# outsim_nano.net
KiCad netlist of a schematic drawn in EAGLE
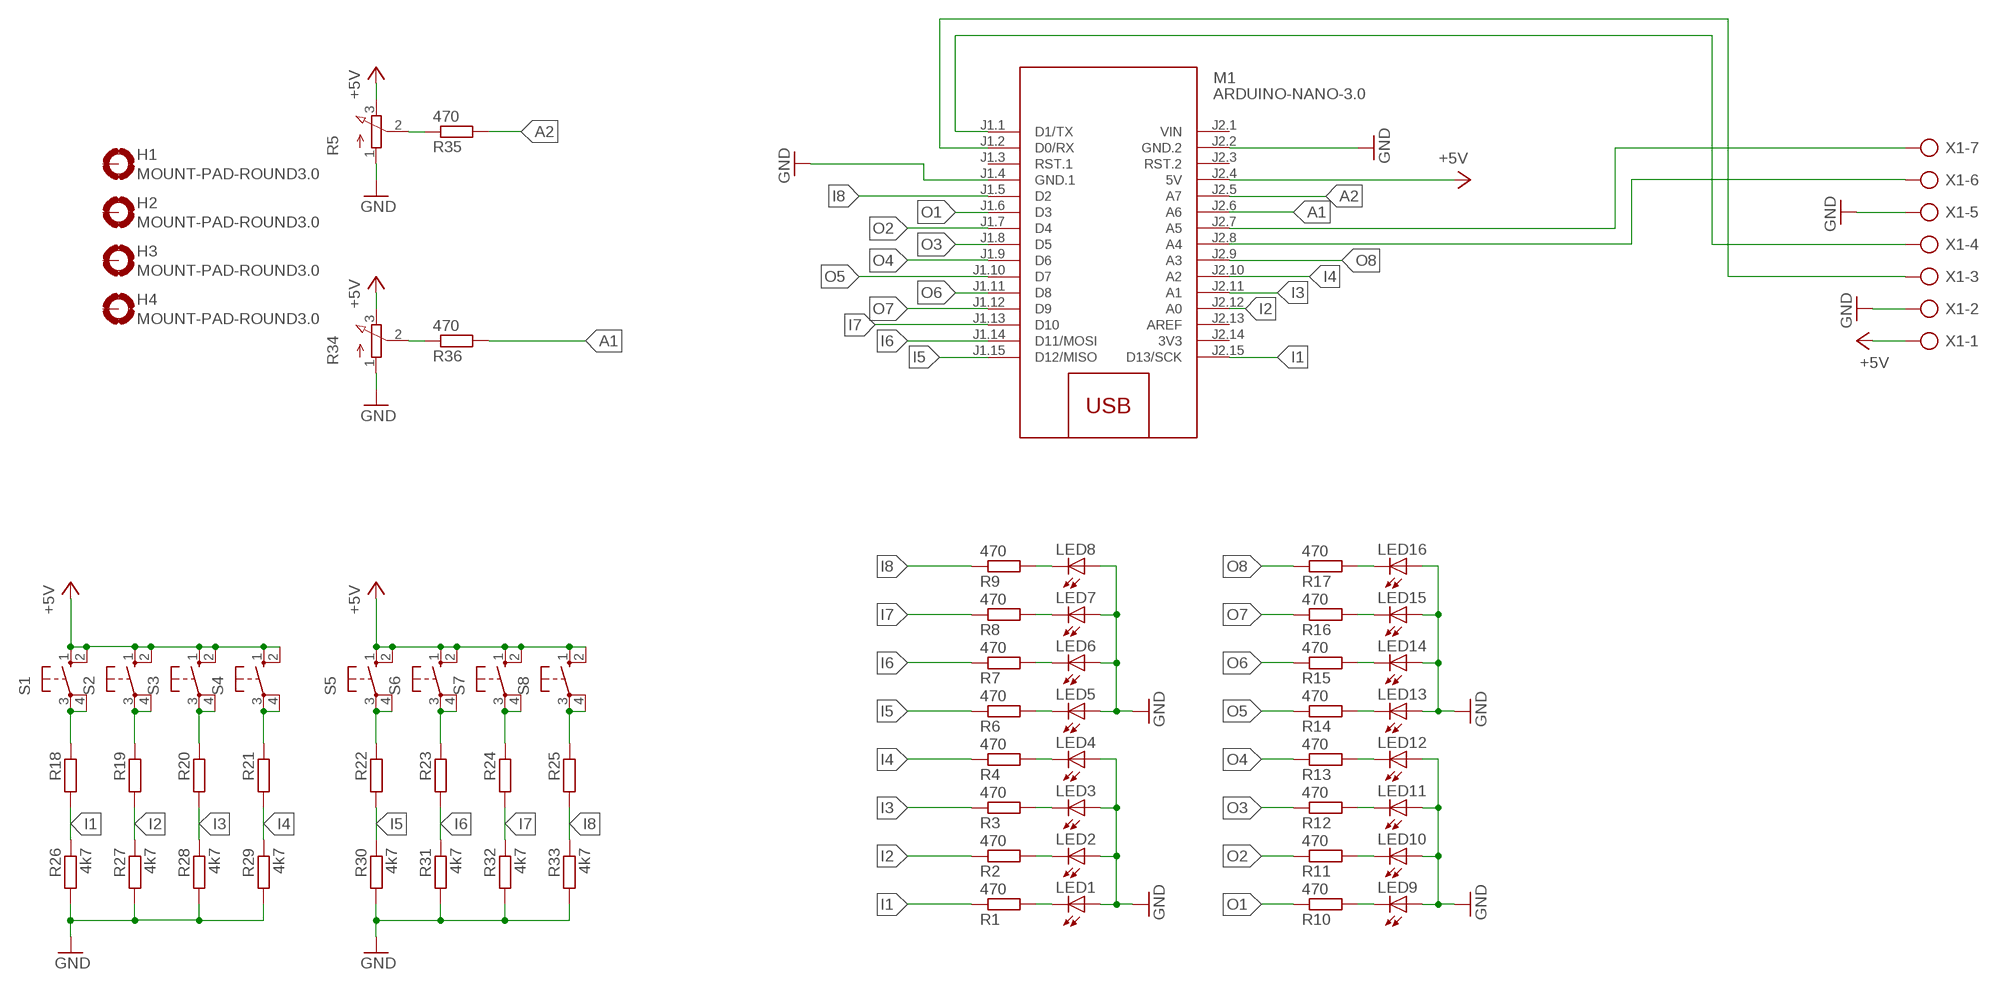
[diagram p0: schematic, sheet 1]

(export (version "E")
  (design (tool "Eeschema 10.0.6"))
  (components
    (comp (ref "H1")
      (value "MOUNT-PAD-ROUND3.0")
      (footprint "eagle-import:3,0-PAD")
      (libsource (lib "eagle-import") (part "MOUNT-PAD-ROUND3.0"))
    )
    (comp (ref "H2")
      (value "MOUNT-PAD-ROUND3.0")
      (footprint "eagle-import:3,0-PAD")
      (libsource (lib "eagle-import") (part "MOUNT-PAD-ROUND3.0"))
    )
    (comp (ref "H3")
      (value "MOUNT-PAD-ROUND3.0")
      (footprint "eagle-import:3,0-PAD")
      (libsource (lib "eagle-import") (part "MOUNT-PAD-ROUND3.0"))
    )
    (comp (ref "H4")
      (value "MOUNT-PAD-ROUND3.0")
      (footprint "eagle-import:3,0-PAD")
      (libsource (lib "eagle-import") (part "MOUNT-PAD-ROUND3.0"))
    )
    (comp (ref "LED1")
      (value "LED5MM")
      (footprint "eagle-import:LED5MM")
      (libsource (lib "eagle-import") (part "LED5MM"))
    )
    (comp (ref "LED2")
      (value "LED5MM")
      (footprint "eagle-import:LED5MM")
      (libsource (lib "eagle-import") (part "LED5MM"))
    )
    (comp (ref "LED3")
      (value "LED5MM")
      (footprint "eagle-import:LED5MM")
      (libsource (lib "eagle-import") (part "LED5MM"))
    )
    (comp (ref "LED4")
      (value "LED5MM")
      (footprint "eagle-import:LED5MM")
      (libsource (lib "eagle-import") (part "LED5MM"))
    )
    (comp (ref "LED5")
      (value "LED5MM")
      (footprint "eagle-import:LED5MM")
      (libsource (lib "eagle-import") (part "LED5MM"))
    )
    (comp (ref "LED6")
      (value "LED5MM")
      (footprint "eagle-import:LED5MM")
      (libsource (lib "eagle-import") (part "LED5MM"))
    )
    (comp (ref "LED7")
      (value "LED5MM")
      (footprint "eagle-import:LED5MM")
      (libsource (lib "eagle-import") (part "LED5MM"))
    )
    (comp (ref "LED8")
      (value "LED5MM")
      (footprint "eagle-import:LED5MM")
      (libsource (lib "eagle-import") (part "LED5MM"))
    )
    (comp (ref "LED9")
      (value "LED5MM")
      (footprint "eagle-import:LED5MM")
      (libsource (lib "eagle-import") (part "LED5MM"))
    )
    (comp (ref "LED10")
      (value "LED5MM")
      (footprint "eagle-import:LED5MM")
      (libsource (lib "eagle-import") (part "LED5MM"))
    )
    (comp (ref "LED11")
      (value "LED5MM")
      (footprint "eagle-import:LED5MM")
      (libsource (lib "eagle-import") (part "LED5MM"))
    )
    (comp (ref "LED12")
      (value "LED5MM")
      (footprint "eagle-import:LED5MM")
      (libsource (lib "eagle-import") (part "LED5MM"))
    )
    (comp (ref "LED13")
      (value "LED5MM")
      (footprint "eagle-import:LED5MM")
      (libsource (lib "eagle-import") (part "LED5MM"))
    )
    (comp (ref "LED14")
      (value "LED5MM")
      (footprint "eagle-import:LED5MM")
      (libsource (lib "eagle-import") (part "LED5MM"))
    )
    (comp (ref "LED15")
      (value "LED5MM")
      (footprint "eagle-import:LED5MM")
      (libsource (lib "eagle-import") (part "LED5MM"))
    )
    (comp (ref "LED16")
      (value "LED5MM")
      (footprint "eagle-import:LED5MM")
      (libsource (lib "eagle-import") (part "LED5MM"))
    )
    (comp (ref "M1")
      (value "ARDUINO-NANO-3.0")
      (footprint "eagle-import:ARDUINO-NANO-3.0")
      (libsource (lib "eagle-import") (part "ARDUINO-NANO-3.0"))
    )
    (comp (ref "R1")
      (value "470")
      (footprint "eagle-import:0207_10")
      (libsource (lib "eagle-import") (part "R-EU_0207/10"))
    )
    (comp (ref "R2")
      (value "470")
      (footprint "eagle-import:0207_10")
      (libsource (lib "eagle-import") (part "R-EU_0207/10"))
    )
    (comp (ref "R3")
      (value "470")
      (footprint "eagle-import:0207_10")
      (libsource (lib "eagle-import") (part "R-EU_0207/10"))
    )
    (comp (ref "R4")
      (value "470")
      (footprint "eagle-import:0207_10")
      (libsource (lib "eagle-import") (part "R-EU_0207/10"))
    )
    (comp (ref "R5")
      (value "3RP/1610N")
      (footprint "eagle-import:3RP_1610N")
      (libsource (lib "eagle-import") (part "3RP/1610N"))
    )
    (comp (ref "R6")
      (value "470")
      (footprint "eagle-import:0207_10")
      (libsource (lib "eagle-import") (part "R-EU_0207/10"))
    )
    (comp (ref "R7")
      (value "470")
      (footprint "eagle-import:0207_10")
      (libsource (lib "eagle-import") (part "R-EU_0207/10"))
    )
    (comp (ref "R8")
      (value "470")
      (footprint "eagle-import:0207_10")
      (libsource (lib "eagle-import") (part "R-EU_0207/10"))
    )
    (comp (ref "R9")
      (value "470")
      (footprint "eagle-import:0207_10")
      (libsource (lib "eagle-import") (part "R-EU_0207/10"))
    )
    (comp (ref "R10")
      (value "470")
      (footprint "eagle-import:0207_10")
      (libsource (lib "eagle-import") (part "R-EU_0207/10"))
    )
    (comp (ref "R11")
      (value "470")
      (footprint "eagle-import:0207_10")
      (libsource (lib "eagle-import") (part "R-EU_0207/10"))
    )
    (comp (ref "R12")
      (value "470")
      (footprint "eagle-import:0207_10")
      (libsource (lib "eagle-import") (part "R-EU_0207/10"))
    )
    (comp (ref "R13")
      (value "470")
      (footprint "eagle-import:0207_10")
      (libsource (lib "eagle-import") (part "R-EU_0207/10"))
    )
    (comp (ref "R14")
      (value "470")
      (footprint "eagle-import:0207_10")
      (libsource (lib "eagle-import") (part "R-EU_0207/10"))
    )
    (comp (ref "R15")
      (value "470")
      (footprint "eagle-import:0207_10")
      (libsource (lib "eagle-import") (part "R-EU_0207/10"))
    )
    (comp (ref "R16")
      (value "470")
      (footprint "eagle-import:0207_10")
      (libsource (lib "eagle-import") (part "R-EU_0207/10"))
    )
    (comp (ref "R17")
      (value "470")
      (footprint "eagle-import:0207_10")
      (libsource (lib "eagle-import") (part "R-EU_0207/10"))
    )
    (comp (ref "R18")
      (value "R-EU_0207/10")
      (footprint "eagle-import:0207_10")
      (libsource (lib "eagle-import") (part "R-EU_0207/10"))
    )
    (comp (ref "R19")
      (value "R-EU_0207/10")
      (footprint "eagle-import:0207_10")
      (libsource (lib "eagle-import") (part "R-EU_0207/10"))
    )
    (comp (ref "R20")
      (value "R-EU_0207/10")
      (footprint "eagle-import:0207_10")
      (libsource (lib "eagle-import") (part "R-EU_0207/10"))
    )
    (comp (ref "R21")
      (value "R-EU_0207/10")
      (footprint "eagle-import:0207_10")
      (libsource (lib "eagle-import") (part "R-EU_0207/10"))
    )
    (comp (ref "R22")
      (value "R-EU_0207/10")
      (footprint "eagle-import:0207_10")
      (libsource (lib "eagle-import") (part "R-EU_0207/10"))
    )
    (comp (ref "R23")
      (value "R-EU_0207/10")
      (footprint "eagle-import:0207_10")
      (libsource (lib "eagle-import") (part "R-EU_0207/10"))
    )
    (comp (ref "R24")
      (value "R-EU_0207/10")
      (footprint "eagle-import:0207_10")
      (libsource (lib "eagle-import") (part "R-EU_0207/10"))
    )
    (comp (ref "R25")
      (value "R-EU_0207/10")
      (footprint "eagle-import:0207_10")
      (libsource (lib "eagle-import") (part "R-EU_0207/10"))
    )
    (comp (ref "R26")
      (value "4k7")
      (footprint "eagle-import:0207_10")
      (libsource (lib "eagle-import") (part "R-EU_0207/10"))
    )
    (comp (ref "R27")
      (value "4k7")
      (footprint "eagle-import:0207_10")
      (libsource (lib "eagle-import") (part "R-EU_0207/10"))
    )
    (comp (ref "R28")
      (value "4k7")
      (footprint "eagle-import:0207_10")
      (libsource (lib "eagle-import") (part "R-EU_0207/10"))
    )
    (comp (ref "R29")
      (value "4k7")
      (footprint "eagle-import:0207_10")
      (libsource (lib "eagle-import") (part "R-EU_0207/10"))
    )
    (comp (ref "R30")
      (value "4k7")
      (footprint "eagle-import:0207_10")
      (libsource (lib "eagle-import") (part "R-EU_0207/10"))
    )
    (comp (ref "R31")
      (value "4k7")
      (footprint "eagle-import:0207_10")
      (libsource (lib "eagle-import") (part "R-EU_0207/10"))
    )
    (comp (ref "R32")
      (value "4k7")
      (footprint "eagle-import:0207_10")
      (libsource (lib "eagle-import") (part "R-EU_0207/10"))
    )
    (comp (ref "R33")
      (value "4k7")
      (footprint "eagle-import:0207_10")
      (libsource (lib "eagle-import") (part "R-EU_0207/10"))
    )
    (comp (ref "R34")
      (value "3RP/1610N")
      (footprint "eagle-import:3RP_1610N")
      (libsource (lib "eagle-import") (part "3RP/1610N"))
    )
    (comp (ref "R35")
      (value "470")
      (footprint "eagle-import:0207_10")
      (libsource (lib "eagle-import") (part "R-EU_0207/10"))
    )
    (comp (ref "R36")
      (value "470")
      (footprint "eagle-import:0207_10")
      (libsource (lib "eagle-import") (part "R-EU_0207/10"))
    )
    (comp (ref "S1")
      (value "10-XX")
      (footprint "eagle-import:B3F-10XX")
      (fields (field (name "MPN") "B3F-1000"))
      (libsource (lib "eagle-import") (part "10-XX"))
    )
    (comp (ref "S2")
      (value "10-XX")
      (footprint "eagle-import:B3F-10XX")
      (fields (field (name "MPN") "B3F-1000"))
      (libsource (lib "eagle-import") (part "10-XX"))
    )
    (comp (ref "S3")
      (value "10-XX")
      (footprint "eagle-import:B3F-10XX")
      (fields (field (name "MPN") "B3F-1000"))
      (libsource (lib "eagle-import") (part "10-XX"))
    )
    (comp (ref "S4")
      (value "10-XX")
      (footprint "eagle-import:B3F-10XX")
      (fields (field (name "MPN") "B3F-1000"))
      (libsource (lib "eagle-import") (part "10-XX"))
    )
    (comp (ref "S5")
      (value "10-XX")
      (footprint "eagle-import:B3F-10XX")
      (fields (field (name "MPN") "B3F-1000"))
      (libsource (lib "eagle-import") (part "10-XX"))
    )
    (comp (ref "S6")
      (value "10-XX")
      (footprint "eagle-import:B3F-10XX")
      (fields (field (name "MPN") "B3F-1000"))
      (libsource (lib "eagle-import") (part "10-XX"))
    )
    (comp (ref "S7")
      (value "10-XX")
      (footprint "eagle-import:B3F-10XX")
      (fields (field (name "MPN") "B3F-1000"))
      (libsource (lib "eagle-import") (part "10-XX"))
    )
    (comp (ref "S8")
      (value "10-XX")
      (footprint "eagle-import:B3F-10XX")
      (fields (field (name "MPN") "B3F-1000"))
      (libsource (lib "eagle-import") (part "10-XX"))
    )
    (comp (ref "X1")
      (value "AK300/7")
      (footprint "eagle-import:AK300_7")
      (libsource (lib "eagle-import") (part "AK300/7"))
    )
  )
  (nets
    (net (code "1") (name "+5V") (class "Default")
      (node (ref "M1") (pin "J2.4") (pinfunction "5V_J2.4") (pintype "power_in"))
      (node (ref "R34") (pin "3") (pinfunction "E_3") (pintype "passive"))
      (node (ref "R5") (pin "3") (pinfunction "E_3") (pintype "passive"))
      (node (ref "S1") (pin "1") (pinfunction "S_1") (pintype "passive"))
      (node (ref "S1") (pin "2") (pinfunction "S1_2") (pintype "passive"))
      (node (ref "S2") (pin "1") (pinfunction "S_1") (pintype "passive"))
      (node (ref "S2") (pin "2") (pinfunction "S1_2") (pintype "passive"))
      (node (ref "S3") (pin "1") (pinfunction "S_1") (pintype "passive"))
      (node (ref "S3") (pin "2") (pinfunction "S1_2") (pintype "passive"))
      (node (ref "S4") (pin "1") (pinfunction "S_1") (pintype "passive"))
      (node (ref "S4") (pin "2") (pinfunction "S1_2") (pintype "passive"))
      (node (ref "S5") (pin "1") (pinfunction "S_1") (pintype "passive"))
      (node (ref "S5") (pin "2") (pinfunction "S1_2") (pintype "passive"))
      (node (ref "S6") (pin "1") (pinfunction "S_1") (pintype "passive"))
      (node (ref "S6") (pin "2") (pinfunction "S1_2") (pintype "passive"))
      (node (ref "S7") (pin "1") (pinfunction "S_1") (pintype "passive"))
      (node (ref "S7") (pin "2") (pinfunction "S1_2") (pintype "passive"))
      (node (ref "S8") (pin "1") (pinfunction "S_1") (pintype "passive"))
      (node (ref "S8") (pin "2") (pinfunction "S1_2") (pintype "passive"))
      (node (ref "X1") (pin "1") (pinfunction "KL_1") (pintype "passive"))
    )
    (net (code "2") (name "/3V3") (class "Default")
      (node (ref "M1") (pin "J2.14") (pinfunction "3V3_J2.14") (pintype "power_in"))
    )
    (net (code "3") (name "/VIN") (class "Default")
      (node (ref "M1") (pin "J2.1") (pinfunction "VIN_J2.1") (pintype "power_in"))
    )
    (net (code "4") (name "A1") (class "Default")
      (node (ref "M1") (pin "J2.6") (pinfunction "A6_J2.6") (pintype "bidirectional"))
      (node (ref "R36") (pin "2") (pinfunction "2_2") (pintype "passive"))
    )
    (net (code "5") (name "A2") (class "Default")
      (node (ref "M1") (pin "J2.5") (pinfunction "A7_J2.5") (pintype "bidirectional"))
      (node (ref "R35") (pin "2") (pinfunction "2_2") (pintype "passive"))
    )
    (net (code "6") (name "GND") (class "Default")
      (node (ref "LED1") (pin "A") (pinfunction "A_A") (pintype "passive"))
      (node (ref "LED10") (pin "A") (pinfunction "A_A") (pintype "passive"))
      (node (ref "LED11") (pin "A") (pinfunction "A_A") (pintype "passive"))
      (node (ref "LED12") (pin "A") (pinfunction "A_A") (pintype "passive"))
      (node (ref "LED13") (pin "A") (pinfunction "A_A") (pintype "passive"))
      (node (ref "LED14") (pin "A") (pinfunction "A_A") (pintype "passive"))
      (node (ref "LED15") (pin "A") (pinfunction "A_A") (pintype "passive"))
      (node (ref "LED16") (pin "A") (pinfunction "A_A") (pintype "passive"))
      (node (ref "LED2") (pin "A") (pinfunction "A_A") (pintype "passive"))
      (node (ref "LED3") (pin "A") (pinfunction "A_A") (pintype "passive"))
      (node (ref "LED4") (pin "A") (pinfunction "A_A") (pintype "passive"))
      (node (ref "LED5") (pin "A") (pinfunction "A_A") (pintype "passive"))
      (node (ref "LED6") (pin "A") (pinfunction "A_A") (pintype "passive"))
      (node (ref "LED7") (pin "A") (pinfunction "A_A") (pintype "passive"))
      (node (ref "LED8") (pin "A") (pinfunction "A_A") (pintype "passive"))
      (node (ref "LED9") (pin "A") (pinfunction "A_A") (pintype "passive"))
      (node (ref "M1") (pin "J1.4") (pinfunction "GND.1_J1.4") (pintype "power_in"))
      (node (ref "M1") (pin "J2.2") (pinfunction "GND.2_J2.2") (pintype "power_in"))
      (node (ref "R26") (pin "2") (pinfunction "2_2") (pintype "passive"))
      (node (ref "R27") (pin "2") (pinfunction "2_2") (pintype "passive"))
      (node (ref "R28") (pin "2") (pinfunction "2_2") (pintype "passive"))
      (node (ref "R29") (pin "2") (pinfunction "2_2") (pintype "passive"))
      (node (ref "R30") (pin "2") (pinfunction "2_2") (pintype "passive"))
      (node (ref "R31") (pin "2") (pinfunction "2_2") (pintype "passive"))
      (node (ref "R32") (pin "2") (pinfunction "2_2") (pintype "passive"))
      (node (ref "R33") (pin "2") (pinfunction "2_2") (pintype "passive"))
      (node (ref "R34") (pin "1") (pinfunction "A_1") (pintype "passive"))
      (node (ref "R5") (pin "1") (pinfunction "A_1") (pintype "passive"))
      (node (ref "X1") (pin "2") (pinfunction "KL_2") (pintype "passive"))
      (node (ref "X1") (pin "5") (pinfunction "KL_5") (pintype "passive"))
    )
    (net (code "7") (name "I1") (class "Default")
      (node (ref "M1") (pin "J2.15") (pinfunction "D13/SCK_J2.15") (pintype "bidirectional"))
      (node (ref "R1") (pin "1") (pinfunction "1_1") (pintype "passive"))
      (node (ref "R18") (pin "2") (pinfunction "2_2") (pintype "passive"))
      (node (ref "R26") (pin "1") (pinfunction "1_1") (pintype "passive"))
    )
    (net (code "8") (name "I2") (class "Default")
      (node (ref "M1") (pin "J2.12") (pinfunction "A0_J2.12") (pintype "bidirectional"))
      (node (ref "R19") (pin "2") (pinfunction "2_2") (pintype "passive"))
      (node (ref "R2") (pin "1") (pinfunction "1_1") (pintype "passive"))
      (node (ref "R27") (pin "1") (pinfunction "1_1") (pintype "passive"))
    )
    (net (code "9") (name "I3") (class "Default")
      (node (ref "M1") (pin "J2.11") (pinfunction "A1_J2.11") (pintype "bidirectional"))
      (node (ref "R20") (pin "2") (pinfunction "2_2") (pintype "passive"))
      (node (ref "R28") (pin "1") (pinfunction "1_1") (pintype "passive"))
      (node (ref "R3") (pin "1") (pinfunction "1_1") (pintype "passive"))
    )
    (net (code "10") (name "I4") (class "Default")
      (node (ref "M1") (pin "J2.10") (pinfunction "A2_J2.10") (pintype "bidirectional"))
      (node (ref "R21") (pin "2") (pinfunction "2_2") (pintype "passive"))
      (node (ref "R29") (pin "1") (pinfunction "1_1") (pintype "passive"))
      (node (ref "R4") (pin "1") (pinfunction "1_1") (pintype "passive"))
    )
    (net (code "11") (name "I5") (class "Default")
      (node (ref "M1") (pin "J1.15") (pinfunction "D12/MISO_J1.15") (pintype "bidirectional"))
      (node (ref "R22") (pin "2") (pinfunction "2_2") (pintype "passive"))
      (node (ref "R30") (pin "1") (pinfunction "1_1") (pintype "passive"))
      (node (ref "R6") (pin "1") (pinfunction "1_1") (pintype "passive"))
    )
    (net (code "12") (name "I6") (class "Default")
      (node (ref "M1") (pin "J1.14") (pinfunction "D11/MOSI_J1.14") (pintype "bidirectional"))
      (node (ref "R23") (pin "2") (pinfunction "2_2") (pintype "passive"))
      (node (ref "R31") (pin "1") (pinfunction "1_1") (pintype "passive"))
      (node (ref "R7") (pin "1") (pinfunction "1_1") (pintype "passive"))
    )
    (net (code "13") (name "I7") (class "Default")
      (node (ref "M1") (pin "J1.13") (pinfunction "D10_J1.13") (pintype "bidirectional"))
      (node (ref "R24") (pin "2") (pinfunction "2_2") (pintype "passive"))
      (node (ref "R32") (pin "1") (pinfunction "1_1") (pintype "passive"))
      (node (ref "R8") (pin "1") (pinfunction "1_1") (pintype "passive"))
    )
    (net (code "14") (name "I8") (class "Default")
      (node (ref "M1") (pin "J1.5") (pinfunction "D2_J1.5") (pintype "bidirectional"))
      (node (ref "R25") (pin "2") (pinfunction "2_2") (pintype "passive"))
      (node (ref "R33") (pin "1") (pinfunction "1_1") (pintype "passive"))
      (node (ref "R9") (pin "1") (pinfunction "1_1") (pintype "passive"))
    )
    (net (code "15") (name "Net-(LED1-C)") (class "Default")
      (node (ref "LED1") (pin "K") (pinfunction "C_K") (pintype "passive"))
      (node (ref "R1") (pin "2") (pinfunction "2_2") (pintype "passive"))
    )
    (net (code "16") (name "Net-(LED2-C)") (class "Default")
      (node (ref "LED2") (pin "K") (pinfunction "C_K") (pintype "passive"))
      (node (ref "R2") (pin "2") (pinfunction "2_2") (pintype "passive"))
    )
    (net (code "17") (name "Net-(LED3-C)") (class "Default")
      (node (ref "LED3") (pin "K") (pinfunction "C_K") (pintype "passive"))
      (node (ref "R3") (pin "2") (pinfunction "2_2") (pintype "passive"))
    )
    (net (code "18") (name "Net-(LED4-C)") (class "Default")
      (node (ref "LED4") (pin "K") (pinfunction "C_K") (pintype "passive"))
      (node (ref "R4") (pin "2") (pinfunction "2_2") (pintype "passive"))
    )
    (net (code "19") (name "Net-(LED5-C)") (class "Default")
      (node (ref "LED5") (pin "K") (pinfunction "C_K") (pintype "passive"))
      (node (ref "R6") (pin "2") (pinfunction "2_2") (pintype "passive"))
    )
    (net (code "20") (name "Net-(LED6-C)") (class "Default")
      (node (ref "LED6") (pin "K") (pinfunction "C_K") (pintype "passive"))
      (node (ref "R7") (pin "2") (pinfunction "2_2") (pintype "passive"))
    )
    (net (code "21") (name "Net-(LED7-C)") (class "Default")
      (node (ref "LED7") (pin "K") (pinfunction "C_K") (pintype "passive"))
      (node (ref "R8") (pin "2") (pinfunction "2_2") (pintype "passive"))
    )
    (net (code "22") (name "Net-(LED8-C)") (class "Default")
      (node (ref "LED8") (pin "K") (pinfunction "C_K") (pintype "passive"))
      (node (ref "R9") (pin "2") (pinfunction "2_2") (pintype "passive"))
    )
    (net (code "23") (name "Net-(LED9-C)") (class "Default")
      (node (ref "LED9") (pin "K") (pinfunction "C_K") (pintype "passive"))
      (node (ref "R10") (pin "2") (pinfunction "2_2") (pintype "passive"))
    )
    (net (code "24") (name "Net-(LED10-C)") (class "Default")
      (node (ref "LED10") (pin "K") (pinfunction "C_K") (pintype "passive"))
      (node (ref "R11") (pin "2") (pinfunction "2_2") (pintype "passive"))
    )
    (net (code "25") (name "Net-(LED11-C)") (class "Default")
      (node (ref "LED11") (pin "K") (pinfunction "C_K") (pintype "passive"))
      (node (ref "R12") (pin "2") (pinfunction "2_2") (pintype "passive"))
    )
    (net (code "26") (name "Net-(LED12-C)") (class "Default")
      (node (ref "LED12") (pin "K") (pinfunction "C_K") (pintype "passive"))
      (node (ref "R13") (pin "2") (pinfunction "2_2") (pintype "passive"))
    )
    (net (code "27") (name "Net-(LED13-C)") (class "Default")
      (node (ref "LED13") (pin "K") (pinfunction "C_K") (pintype "passive"))
      (node (ref "R14") (pin "2") (pinfunction "2_2") (pintype "passive"))
    )
    (net (code "28") (name "Net-(LED14-C)") (class "Default")
      (node (ref "LED14") (pin "K") (pinfunction "C_K") (pintype "passive"))
      (node (ref "R15") (pin "2") (pinfunction "2_2") (pintype "passive"))
    )
    (net (code "29") (name "Net-(LED15-C)") (class "Default")
      (node (ref "LED15") (pin "K") (pinfunction "C_K") (pintype "passive"))
      (node (ref "R16") (pin "2") (pinfunction "2_2") (pintype "passive"))
    )
    (net (code "30") (name "Net-(LED16-C)") (class "Default")
      (node (ref "LED16") (pin "K") (pinfunction "C_K") (pintype "passive"))
      (node (ref "R17") (pin "2") (pinfunction "2_2") (pintype "passive"))
    )
    (net (code "31") (name "Net-(M1-A4)") (class "Default")
      (node (ref "M1") (pin "J2.8") (pinfunction "A4_J2.8") (pintype "bidirectional"))
      (node (ref "X1") (pin "6") (pinfunction "KL_6") (pintype "passive"))
    )
    (net (code "32") (name "Net-(M1-A5)") (class "Default")
      (node (ref "M1") (pin "J2.7") (pinfunction "A5_J2.7") (pintype "bidirectional"))
      (node (ref "X1") (pin "7") (pinfunction "KL_7") (pintype "passive"))
    )
    (net (code "33") (name "Net-(M1-D0{slash}RX)") (class "Default")
      (node (ref "M1") (pin "J1.2") (pinfunction "D0/RX_J1.2") (pintype "bidirectional"))
      (node (ref "X1") (pin "3") (pinfunction "KL_3") (pintype "passive"))
    )
    (net (code "34") (name "Net-(M1-D1{slash}TX)") (class "Default")
      (node (ref "M1") (pin "J1.1") (pinfunction "D1/TX_J1.1") (pintype "bidirectional"))
      (node (ref "X1") (pin "4") (pinfunction "KL_4") (pintype "passive"))
    )
    (net (code "35") (name "Net-(R5-S)") (class "Default")
      (node (ref "R35") (pin "1") (pinfunction "1_1") (pintype "passive"))
      (node (ref "R5") (pin "2") (pinfunction "S_2") (pintype "passive"))
    )
    (net (code "36") (name "Net-(R34-S)") (class "Default")
      (node (ref "R34") (pin "2") (pinfunction "S_2") (pintype "passive"))
      (node (ref "R36") (pin "1") (pinfunction "1_1") (pintype "passive"))
    )
    (net (code "37") (name "Net-(S1-P)") (class "Default")
      (node (ref "R18") (pin "1") (pinfunction "1_1") (pintype "passive"))
      (node (ref "S1") (pin "3") (pinfunction "P_3") (pintype "passive"))
      (node (ref "S1") (pin "4") (pinfunction "P1_4") (pintype "passive"))
    )
    (net (code "38") (name "Net-(S2-P)") (class "Default")
      (node (ref "R19") (pin "1") (pinfunction "1_1") (pintype "passive"))
      (node (ref "S2") (pin "3") (pinfunction "P_3") (pintype "passive"))
      (node (ref "S2") (pin "4") (pinfunction "P1_4") (pintype "passive"))
    )
    (net (code "39") (name "Net-(S3-P)") (class "Default")
      (node (ref "R20") (pin "1") (pinfunction "1_1") (pintype "passive"))
      (node (ref "S3") (pin "3") (pinfunction "P_3") (pintype "passive"))
      (node (ref "S3") (pin "4") (pinfunction "P1_4") (pintype "passive"))
    )
    (net (code "40") (name "Net-(S4-P)") (class "Default")
      (node (ref "R21") (pin "1") (pinfunction "1_1") (pintype "passive"))
      (node (ref "S4") (pin "3") (pinfunction "P_3") (pintype "passive"))
      (node (ref "S4") (pin "4") (pinfunction "P1_4") (pintype "passive"))
    )
    (net (code "41") (name "Net-(S5-P)") (class "Default")
      (node (ref "R22") (pin "1") (pinfunction "1_1") (pintype "passive"))
      (node (ref "S5") (pin "3") (pinfunction "P_3") (pintype "passive"))
      (node (ref "S5") (pin "4") (pinfunction "P1_4") (pintype "passive"))
    )
    (net (code "42") (name "Net-(S6-P)") (class "Default")
      (node (ref "R23") (pin "1") (pinfunction "1_1") (pintype "passive"))
      (node (ref "S6") (pin "3") (pinfunction "P_3") (pintype "passive"))
      (node (ref "S6") (pin "4") (pinfunction "P1_4") (pintype "passive"))
    )
    (net (code "43") (name "Net-(S7-P)") (class "Default")
      (node (ref "R24") (pin "1") (pinfunction "1_1") (pintype "passive"))
      (node (ref "S7") (pin "3") (pinfunction "P_3") (pintype "passive"))
      (node (ref "S7") (pin "4") (pinfunction "P1_4") (pintype "passive"))
    )
    (net (code "44") (name "Net-(S8-P)") (class "Default")
      (node (ref "R25") (pin "1") (pinfunction "1_1") (pintype "passive"))
      (node (ref "S8") (pin "3") (pinfunction "P_3") (pintype "passive"))
      (node (ref "S8") (pin "4") (pinfunction "P1_4") (pintype "passive"))
    )
    (net (code "45") (name "O1") (class "Default")
      (node (ref "M1") (pin "J1.6") (pinfunction "D3_J1.6") (pintype "bidirectional"))
      (node (ref "R10") (pin "1") (pinfunction "1_1") (pintype "passive"))
    )
    (net (code "46") (name "O2") (class "Default")
      (node (ref "M1") (pin "J1.7") (pinfunction "D4_J1.7") (pintype "bidirectional"))
      (node (ref "R11") (pin "1") (pinfunction "1_1") (pintype "passive"))
    )
    (net (code "47") (name "O3") (class "Default")
      (node (ref "M1") (pin "J1.8") (pinfunction "D5_J1.8") (pintype "bidirectional"))
      (node (ref "R12") (pin "1") (pinfunction "1_1") (pintype "passive"))
    )
    (net (code "48") (name "O4") (class "Default")
      (node (ref "M1") (pin "J1.9") (pinfunction "D6_J1.9") (pintype "bidirectional"))
      (node (ref "R13") (pin "1") (pinfunction "1_1") (pintype "passive"))
    )
    (net (code "49") (name "O5") (class "Default")
      (node (ref "M1") (pin "J1.10") (pinfunction "D7_J1.10") (pintype "bidirectional"))
      (node (ref "R14") (pin "1") (pinfunction "1_1") (pintype "passive"))
    )
    (net (code "50") (name "O6") (class "Default")
      (node (ref "M1") (pin "J1.11") (pinfunction "D8_J1.11") (pintype "bidirectional"))
      (node (ref "R15") (pin "1") (pinfunction "1_1") (pintype "passive"))
    )
    (net (code "51") (name "O7") (class "Default")
      (node (ref "M1") (pin "J1.12") (pinfunction "D9_J1.12") (pintype "bidirectional"))
      (node (ref "R16") (pin "1") (pinfunction "1_1") (pintype "passive"))
    )
    (net (code "52") (name "O8") (class "Default")
      (node (ref "M1") (pin "J2.9") (pinfunction "A3_J2.9") (pintype "bidirectional"))
      (node (ref "R17") (pin "1") (pinfunction "1_1") (pintype "passive"))
    )
    (net (code "53") (name "unconnected-(H1-MOUNT-PadB3,0)") (class "Default")
      (node (ref "H1") (pin "B3,0") (pinfunction "MOUNT_B3,0") (pintype "passive"))
    )
    (net (code "54") (name "unconnected-(H2-MOUNT-PadB3,0)") (class "Default")
      (node (ref "H2") (pin "B3,0") (pinfunction "MOUNT_B3,0") (pintype "passive"))
    )
    (net (code "55") (name "unconnected-(H3-MOUNT-PadB3,0)") (class "Default")
      (node (ref "H3") (pin "B3,0") (pinfunction "MOUNT_B3,0") (pintype "passive"))
    )
    (net (code "56") (name "unconnected-(H4-MOUNT-PadB3,0)") (class "Default")
      (node (ref "H4") (pin "B3,0") (pinfunction "MOUNT_B3,0") (pintype "passive"))
    )
    (net (code "57") (name "unconnected-(M1-AREF-PadJ2.13)") (class "Default")
      (node (ref "M1") (pin "J2.13") (pinfunction "AREF_J2.13") (pintype "bidirectional"))
    )
    (net (code "58") (name "unconnected-(M1-RST.1-PadJ1.3)") (class "Default")
      (node (ref "M1") (pin "J1.3") (pinfunction "RST.1_J1.3") (pintype "bidirectional"))
    )
    (net (code "59") (name "unconnected-(M1-RST.2-PadJ2.3)") (class "Default")
      (node (ref "M1") (pin "J2.3") (pinfunction "RST.2_J2.3") (pintype "bidirectional"))
    )
  )
)
